# PushButtons.net
KiCad netlist of a schematic drawn in Altium Designer
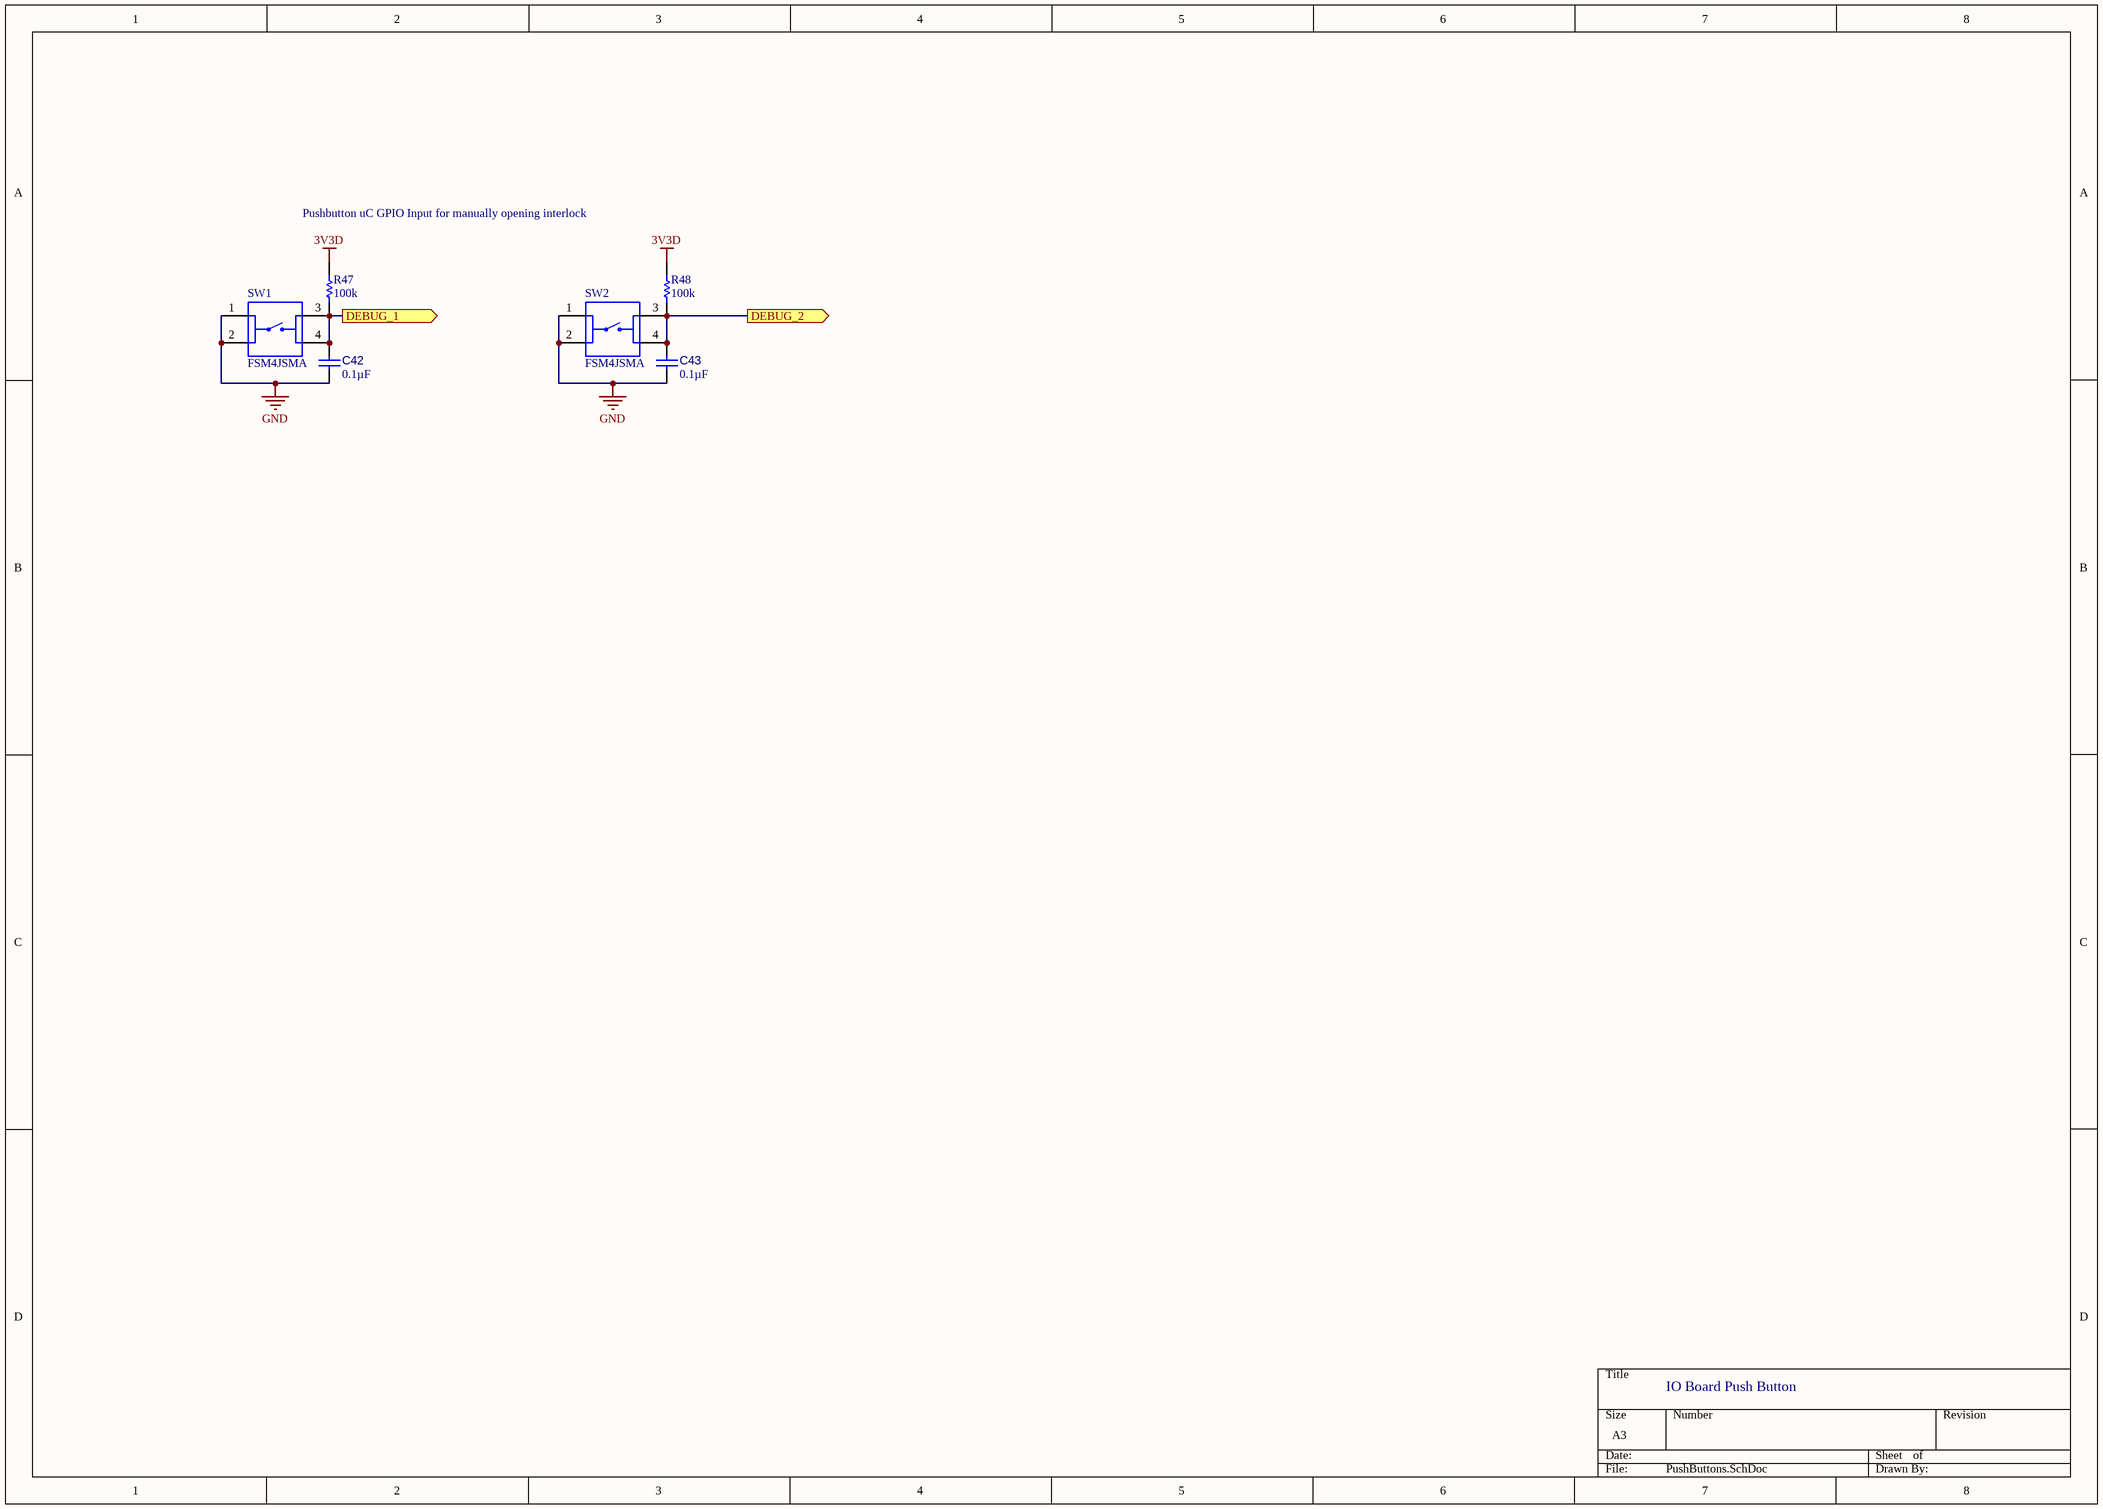
[diagram p0: PushButtons.SchDoc]

(export (version "E")
  (design (tool "Eeschema 10.0.6"))
  (components
    (comp (ref "C42")
      (value "0.1µF")
      (footprint "CAPC2013X145X50ML20T25")
      (description "Chip Capacitor, 0.1 uF, +/-10%, 25 V, 0805 (2012 Metric)")
      (fields
        (field (name "MANUFACTURER") "KEMET")
        (field (name "MANUFACTURER PART NUMBER") "C0805C104K3RACTU")
      )
      (libsource (lib "Caltech FSAE") (part "CAP-NP-2"))
    )
    (comp (ref "C43")
      (value "0.1µF")
      (footprint "CAPC2013X145X50ML20T25")
      (description "Chip Capacitor, 0.1 uF, +/-10%, 25 V, 0805 (2012 Metric)")
      (fields
        (field (name "MANUFACTURER") "KEMET")
        (field (name "MANUFACTURER PART NUMBER") "C0805C104K3RACTU")
      )
      (libsource (lib "Caltech FSAE") (part "CAP-NP-2"))
    )
    (comp (ref "R47")
      (value "100k")
      (footprint "RESC2013X50X35ML15T15")
      (description "Chip Resistor, 100k Ohm, +/- 1%, 125 mW, -55 to 155 degC, 0805 (2012 Metric)")
      (fields
        (field (name "MANUFACTURER") "Yageo")
        (field (name "MANUFACTURER PART NUMBER") "RC0805FR-07100KL")
      )
      (libsource (lib "Caltech FSAE") (part "RES-2"))
    )
    (comp (ref "R48")
      (value "100k")
      (footprint "RESC2013X50X35ML15T15")
      (description "Chip Resistor, 100k Ohm, +/- 1%, 125 mW, -55 to 155 degC, 0805 (2012 Metric)")
      (fields
        (field (name "MANUFACTURER") "Yageo")
        (field (name "MANUFACTURER PART NUMBER") "RC0805FR-07100KL")
      )
      (libsource (lib "Caltech FSAE") (part "RES-2"))
    )
    (comp (ref "SW1")
      (value "FSM4JSMA")
      (footprint "TE_FSM4JSMA")
      (description "Tactile Switch SPST-NO Top Actuated Surface Mount")
      (fields (field (name "MF") "TE Connectivity"))
      (libsource (lib "uControllerTemplate2021") (part "FSM4JSMA"))
    )
    (comp (ref "SW2")
      (value "FSM4JSMA")
      (footprint "TE_FSM4JSMA")
      (description "Tactile Switch SPST-NO Top Actuated Surface Mount")
      (fields (field (name "MF") "TE Connectivity"))
      (libsource (lib "uControllerTemplate2021") (part "FSM4JSMA"))
    )
  )
  (nets
    (net (code "1") (name "/DEBUG_1") (class "Default")
      (node (ref "C42") (pin "2") (pinfunction "2_2") (pintype "passive"))
      (node (ref "R47") (pin "1") (pinfunction "1_1") (pintype "passive"))
      (node (ref "SW1") (pin "3") (pinfunction "3_3") (pintype "passive"))
      (node (ref "SW1") (pin "4") (pinfunction "4_4") (pintype "passive"))
    )
    (net (code "2") (name "/DEBUG_2") (class "Default")
      (node (ref "C43") (pin "2") (pinfunction "2_2") (pintype "passive"))
      (node (ref "R48") (pin "1") (pinfunction "1_1") (pintype "passive"))
      (node (ref "SW2") (pin "3") (pinfunction "3_3") (pintype "passive"))
      (node (ref "SW2") (pin "4") (pinfunction "4_4") (pintype "passive"))
    )
    (net (code "3") (name "3V3D") (class "Default")
      (node (ref "R47") (pin "2") (pinfunction "2_2") (pintype "passive"))
      (node (ref "R48") (pin "2") (pinfunction "2_2") (pintype "passive"))
    )
    (net (code "4") (name "GND") (class "Default")
      (node (ref "C42") (pin "1") (pinfunction "1_1") (pintype "passive"))
      (node (ref "C43") (pin "1") (pinfunction "1_1") (pintype "passive"))
      (node (ref "SW1") (pin "1") (pinfunction "1_1") (pintype "passive"))
      (node (ref "SW1") (pin "2") (pinfunction "2_2") (pintype "passive"))
      (node (ref "SW2") (pin "1") (pinfunction "1_1") (pintype "passive"))
      (node (ref "SW2") (pin "2") (pinfunction "2_2") (pintype "passive"))
    )
  )
)
